# serial_to_usb_interface_0_2.net
KiCad netlist of a schematic drawn in EAGLE
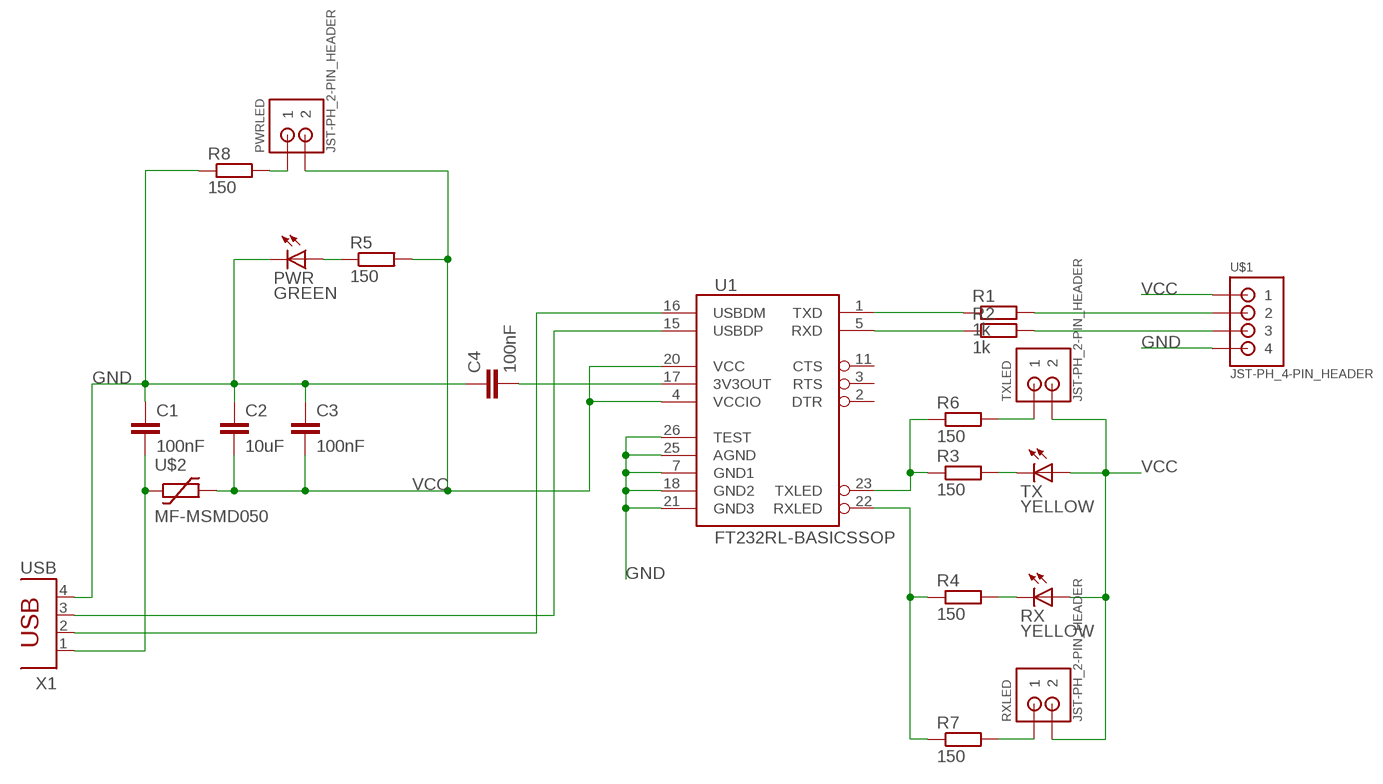
[diagram p0: schematic, sheet 1]

(export (version "E")
  (design (tool "Eeschema 10.0.6"))
  (components
    (comp (ref "C1")
      (value "100nF")
      (footprint "eagle-import:C1206")
      (libsource (lib "eagle-import") (part "C-EUC1206"))
    )
    (comp (ref "C2")
      (value "10uF")
      (footprint "eagle-import:C1206")
      (libsource (lib "eagle-import") (part "C-EUC1206"))
    )
    (comp (ref "C3")
      (value "100nF")
      (footprint "eagle-import:C1206")
      (libsource (lib "eagle-import") (part "C-EUC1206"))
    )
    (comp (ref "C4")
      (value "100nF")
      (footprint "eagle-import:C1206")
      (libsource (lib "eagle-import") (part "C-EUC1206"))
    )
    (comp (ref "PWR")
      (value "GREEN")
      (footprint "eagle-import:CHIPLED_0805")
      (libsource (lib "eagle-import") (part "LEDCHIPLED_0805"))
    )
    (comp (ref "PWRLED")
      (value "JST-PH_2-PIN_HEADER")
      (footprint "eagle-import:JST_B2B-PH_HEADER")
      (libsource (lib "eagle-import") (part "JST-PH_2-PIN_HEADER"))
    )
    (comp (ref "R1")
      (value "1k")
      (footprint "eagle-import:R1206")
      (libsource (lib "eagle-import") (part "R-EU_R1206"))
    )
    (comp (ref "R2")
      (value "1k")
      (footprint "eagle-import:R1206")
      (libsource (lib "eagle-import") (part "R-EU_R1206"))
    )
    (comp (ref "R3")
      (value "150")
      (footprint "eagle-import:R1206")
      (libsource (lib "eagle-import") (part "R-EU_R1206"))
    )
    (comp (ref "R4")
      (value "150")
      (footprint "eagle-import:R1206")
      (libsource (lib "eagle-import") (part "R-EU_R1206"))
    )
    (comp (ref "R5")
      (value "150")
      (footprint "eagle-import:R1206")
      (libsource (lib "eagle-import") (part "R-EU_R1206"))
    )
    (comp (ref "R6")
      (value "150")
      (footprint "eagle-import:R1206")
      (libsource (lib "eagle-import") (part "R-EU_R1206"))
    )
    (comp (ref "R7")
      (value "150")
      (footprint "eagle-import:R1206")
      (libsource (lib "eagle-import") (part "R-EU_R1206"))
    )
    (comp (ref "R8")
      (value "150")
      (footprint "eagle-import:R1206")
      (libsource (lib "eagle-import") (part "R-EU_R1206"))
    )
    (comp (ref "RX")
      (value "YELLOW")
      (footprint "eagle-import:CHIPLED_0805")
      (libsource (lib "eagle-import") (part "LEDCHIPLED_0805"))
    )
    (comp (ref "RXLED")
      (value "JST-PH_2-PIN_HEADER")
      (footprint "eagle-import:JST_B2B-PH_HEADER")
      (libsource (lib "eagle-import") (part "JST-PH_2-PIN_HEADER"))
    )
    (comp (ref "TX")
      (value "YELLOW")
      (footprint "eagle-import:CHIPLED_0805")
      (libsource (lib "eagle-import") (part "LEDCHIPLED_0805"))
    )
    (comp (ref "TXLED")
      (value "JST-PH_2-PIN_HEADER")
      (footprint "eagle-import:JST_B2B-PH_HEADER")
      (libsource (lib "eagle-import") (part "JST-PH_2-PIN_HEADER"))
    )
    (comp (ref "U$1")
      (value "JST-PH_4-PIN_HEADER")
      (footprint "eagle-import:JST_B4B-PH_HEADER")
      (libsource (lib "eagle-import") (part "JST-PH_4-PIN_HEADER"))
    )
    (comp (ref "U$2")
      (value "MF-MSMD050")
      (footprint "eagle-import:MF-MSMD050")
      (libsource (lib "eagle-import") (part "MF-MSMD050"))
    )
    (comp (ref "U1")
      (value "FT232RL-BASICSSOP")
      (footprint "eagle-import:SSOP28DB")
      (libsource (lib "eagle-import") (part "FT232RL-BASICSSOP"))
    )
    (comp (ref "X1")
      (value "USB")
      (footprint "eagle-import:PN87520")
      (libsource (lib "eagle-import") (part "PN87520"))
    )
  )
  (nets
    (net (code "1") (name "/GND") (class "Default")
      (node (ref "C1") (pin "1") (pinfunction "1_1") (pintype "passive"))
      (node (ref "C2") (pin "1") (pinfunction "1_1") (pintype "passive"))
      (node (ref "C3") (pin "1") (pinfunction "1_1") (pintype "passive"))
      (node (ref "C4") (pin "1") (pinfunction "1_1") (pintype "passive"))
      (node (ref "PWR") (pin "C") (pinfunction "C_C") (pintype "passive"))
      (node (ref "R8") (pin "1") (pinfunction "1_1") (pintype "passive"))
      (node (ref "U$1") (pin "P4") (pinfunction "4_P4") (pintype "bidirectional"))
      (node (ref "U1") (pin "18") (pinfunction "GND2_18") (pintype "power_in"))
      (node (ref "U1") (pin "21") (pinfunction "GND3_21") (pintype "power_in"))
      (node (ref "U1") (pin "25") (pinfunction "AGND_25") (pintype "power_in"))
      (node (ref "U1") (pin "26") (pinfunction "TEST_26") (pintype "input"))
      (node (ref "U1") (pin "7") (pinfunction "GND1_7") (pintype "power_in"))
      (node (ref "X1") (pin "4") (pinfunction "4_4") (pintype "passive"))
    )
    (net (code "2") (name "/VCC") (class "Default")
      (node (ref "C2") (pin "2") (pinfunction "2_2") (pintype "passive"))
      (node (ref "C3") (pin "2") (pinfunction "2_2") (pintype "passive"))
      (node (ref "PWRLED") (pin "P2") (pinfunction "2_P2") (pintype "bidirectional"))
      (node (ref "R5") (pin "2") (pinfunction "2_2") (pintype "passive"))
      (node (ref "RX") (pin "A") (pinfunction "A_A") (pintype "passive"))
      (node (ref "RXLED") (pin "P2") (pinfunction "2_P2") (pintype "bidirectional"))
      (node (ref "TX") (pin "A") (pinfunction "A_A") (pintype "passive"))
      (node (ref "TXLED") (pin "P2") (pinfunction "2_P2") (pintype "bidirectional"))
      (node (ref "U$1") (pin "P1") (pinfunction "1_P1") (pintype "bidirectional"))
      (node (ref "U$2") (pin "P$2") (pinfunction "2_P$2") (pintype "passive"))
      (node (ref "U1") (pin "20") (pinfunction "VCC_20") (pintype "power_in"))
      (node (ref "U1") (pin "4") (pinfunction "VCCIO_4") (pintype "power_in"))
    )
    (net (code "3") (name "Net-(PWR-PadA)") (class "Default")
      (node (ref "PWR") (pin "A") (pinfunction "A_A") (pintype "passive"))
      (node (ref "R5") (pin "1") (pinfunction "1_1") (pintype "passive"))
    )
    (net (code "4") (name "Net-(PWRLED-1)") (class "Default")
      (node (ref "PWRLED") (pin "P1") (pinfunction "1_P1") (pintype "bidirectional"))
      (node (ref "R8") (pin "2") (pinfunction "2_2") (pintype "passive"))
    )
    (net (code "5") (name "Net-(R3-Pad2)") (class "Default")
      (node (ref "R3") (pin "2") (pinfunction "2_2") (pintype "passive"))
      (node (ref "TX") (pin "C") (pinfunction "C_C") (pintype "passive"))
    )
    (net (code "6") (name "Net-(R4-Pad2)") (class "Default")
      (node (ref "R4") (pin "2") (pinfunction "2_2") (pintype "passive"))
      (node (ref "RX") (pin "C") (pinfunction "C_C") (pintype "passive"))
    )
    (net (code "7") (name "Net-(RXLED-1)") (class "Default")
      (node (ref "R7") (pin "2") (pinfunction "2_2") (pintype "passive"))
      (node (ref "RXLED") (pin "P1") (pinfunction "1_P1") (pintype "bidirectional"))
    )
    (net (code "8") (name "Net-(TXLED-1)") (class "Default")
      (node (ref "R6") (pin "2") (pinfunction "2_2") (pintype "passive"))
      (node (ref "TXLED") (pin "P1") (pinfunction "1_P1") (pintype "bidirectional"))
    )
    (net (code "9") (name "Net-(U$1-2)") (class "Default")
      (node (ref "R1") (pin "2") (pinfunction "2_2") (pintype "passive"))
      (node (ref "U$1") (pin "P2") (pinfunction "2_P2") (pintype "bidirectional"))
    )
    (net (code "10") (name "Net-(U$1-3)") (class "Default")
      (node (ref "R2") (pin "2") (pinfunction "2_2") (pintype "passive"))
      (node (ref "U$1") (pin "P3") (pinfunction "3_P3") (pintype "bidirectional"))
    )
    (net (code "11") (name "Net-(U$2-1)") (class "Default")
      (node (ref "C1") (pin "2") (pinfunction "2_2") (pintype "passive"))
      (node (ref "U$2") (pin "P$1") (pinfunction "1_P$1") (pintype "passive"))
      (node (ref "X1") (pin "1") (pinfunction "1_1") (pintype "passive"))
    )
    (net (code "12") (name "Net-(U1-3V3OUT)") (class "Default")
      (node (ref "C4") (pin "2") (pinfunction "2_2") (pintype "passive"))
      (node (ref "U1") (pin "17") (pinfunction "3V3OUT_17") (pintype "output"))
    )
    (net (code "13") (name "Net-(U1-RXD)") (class "Default")
      (node (ref "R2") (pin "1") (pinfunction "1_1") (pintype "passive"))
      (node (ref "U1") (pin "5") (pinfunction "RXD_5") (pintype "input"))
    )
    (net (code "14") (name "Net-(U1-RXLED)") (class "Default")
      (node (ref "R4") (pin "1") (pinfunction "1_1") (pintype "passive"))
      (node (ref "R7") (pin "1") (pinfunction "1_1") (pintype "passive"))
      (node (ref "U1") (pin "22") (pinfunction "RXLED_22") (pintype "bidirectional"))
    )
    (net (code "15") (name "Net-(U1-TXD)") (class "Default")
      (node (ref "R1") (pin "1") (pinfunction "1_1") (pintype "passive"))
      (node (ref "U1") (pin "1") (pinfunction "TXD_1") (pintype "output"))
    )
    (net (code "16") (name "Net-(U1-TXLED)") (class "Default")
      (node (ref "R3") (pin "1") (pinfunction "1_1") (pintype "passive"))
      (node (ref "R6") (pin "1") (pinfunction "1_1") (pintype "passive"))
      (node (ref "U1") (pin "23") (pinfunction "TXLED_23") (pintype "bidirectional"))
    )
    (net (code "17") (name "Net-(U1-USBDM)") (class "Default")
      (node (ref "U1") (pin "16") (pinfunction "USBDM_16") (pintype "bidirectional"))
      (node (ref "X1") (pin "2") (pinfunction "2_2") (pintype "passive"))
    )
    (net (code "18") (name "Net-(U1-USBDP)") (class "Default")
      (node (ref "U1") (pin "15") (pinfunction "USBDP_15") (pintype "bidirectional"))
      (node (ref "X1") (pin "3") (pinfunction "3_3") (pintype "passive"))
    )
    (net (code "19") (name "unconnected-(U1-CTS-Pad11)") (class "Default")
      (node (ref "U1") (pin "11") (pinfunction "CTS_11") (pintype "bidirectional"))
    )
    (net (code "20") (name "unconnected-(U1-DTR-Pad2)") (class "Default")
      (node (ref "U1") (pin "2") (pinfunction "DTR_2") (pintype "bidirectional"))
    )
    (net (code "21") (name "unconnected-(U1-RTS-Pad3)") (class "Default")
      (node (ref "U1") (pin "3") (pinfunction "RTS_3") (pintype "bidirectional"))
    )
  )
)
